# ESP32_modul.net
KiCad netlist of a schematic drawn in EAGLE
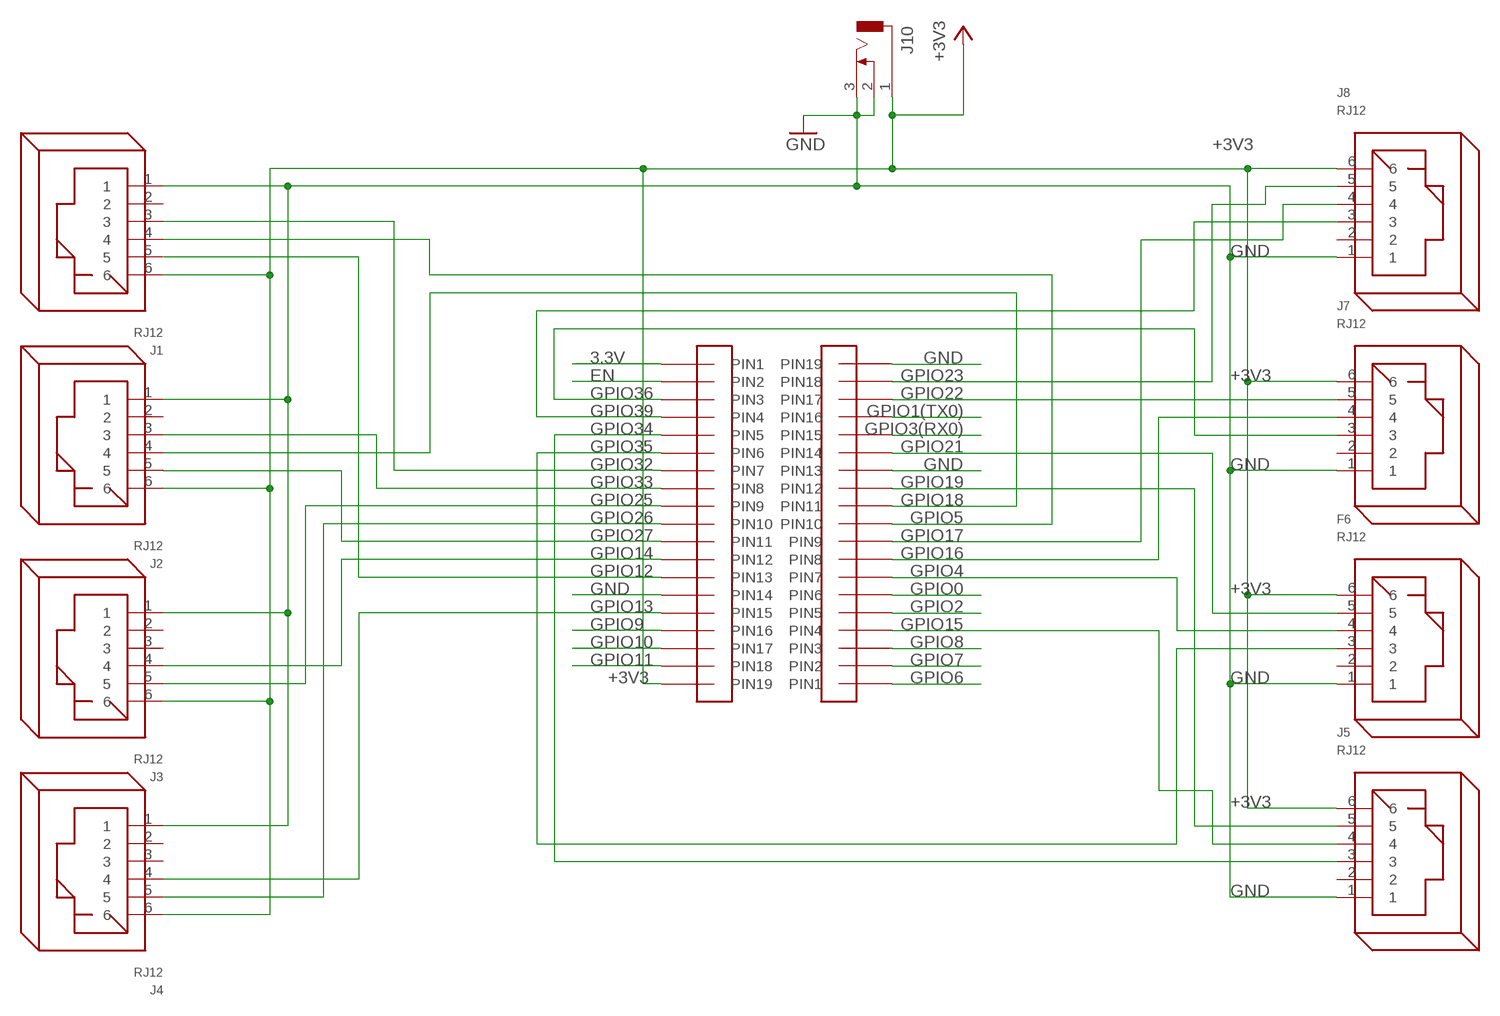
[diagram p0: schematic, sheet 1]

(export (version "E")
  (design (tool "Eeschema 10.0.6"))
  (components
    (comp (ref "F6")
      (value "RJ12")
      (footprint "eagle-import:RJ12")
      (libsource (lib "eagle-import") (part "RJ12"))
    )
    (comp (ref "J1")
      (value "RJ12")
      (footprint "eagle-import:RJ12")
      (libsource (lib "eagle-import") (part "RJ12"))
    )
    (comp (ref "J2")
      (value "RJ12")
      (footprint "eagle-import:RJ12")
      (libsource (lib "eagle-import") (part "RJ12"))
    )
    (comp (ref "J3")
      (value "RJ12")
      (footprint "eagle-import:RJ12")
      (libsource (lib "eagle-import") (part "RJ12"))
    )
    (comp (ref "J4")
      (value "RJ12")
      (footprint "eagle-import:RJ12")
      (libsource (lib "eagle-import") (part "RJ12"))
    )
    (comp (ref "J5")
      (value "RJ12")
      (footprint "eagle-import:RJ12")
      (libsource (lib "eagle-import") (part "RJ12"))
    )
    (comp (ref "J7")
      (value "RJ12")
      (footprint "eagle-import:RJ12")
      (libsource (lib "eagle-import") (part "RJ12"))
    )
    (comp (ref "J8")
      (value "RJ12")
      (footprint "eagle-import:RJ12")
      (libsource (lib "eagle-import") (part "RJ12"))
    )
    (comp (ref "J10")
      (value "DCJ0303")
      (footprint "eagle-import:DCJ0303")
      (libsource (lib "eagle-import") (part "DCJ0303"))
    )
    (comp (ref "U$1")
      (value "F-1X19")
      (footprint "eagle-import:F-1X19")
      (libsource (lib "eagle-import") (part "F-1X19"))
    )
    (comp (ref "U$2")
      (value "F-1X19")
      (footprint "eagle-import:F-1X19")
      (libsource (lib "eagle-import") (part "F-1X19"))
    )
  )
  (nets
    (net (code "1") (name "+3V3") (class "Default")
      (node (ref "F6") (pin "6") (pinfunction "6_6") (pintype "bidirectional"))
      (node (ref "J1") (pin "6") (pinfunction "6_6") (pintype "bidirectional"))
      (node (ref "J10") (pin "1") (pinfunction "1_1") (pintype "passive"))
      (node (ref "J2") (pin "6") (pinfunction "6_6") (pintype "bidirectional"))
      (node (ref "J3") (pin "6") (pinfunction "6_6") (pintype "bidirectional"))
      (node (ref "J4") (pin "6") (pinfunction "6_6") (pintype "bidirectional"))
      (node (ref "J5") (pin "6") (pinfunction "6_6") (pintype "bidirectional"))
      (node (ref "J7") (pin "6") (pinfunction "6_6") (pintype "bidirectional"))
      (node (ref "J8") (pin "6") (pinfunction "6_6") (pintype "bidirectional"))
      (node (ref "U$1") (pin "P$19") (pinfunction "PIN19_P$19") (pintype "bidirectional"))
    )
    (net (code "2") (name "/3.3V") (class "Default")
      (node (ref "U$1") (pin "P$1") (pinfunction "PIN1_P$1") (pintype "bidirectional"))
    )
    (net (code "3") (name "/EN") (class "Default")
      (node (ref "U$1") (pin "P$2") (pinfunction "PIN2_P$2") (pintype "bidirectional"))
    )
    (net (code "4") (name "/GPIO0") (class "Default")
      (node (ref "U$2") (pin "P$6") (pinfunction "PIN6_P$6") (pintype "bidirectional"))
    )
    (net (code "5") (name "/GPIO1(TX0)") (class "Default")
      (node (ref "U$2") (pin "P$16") (pinfunction "PIN16_P$16") (pintype "bidirectional"))
    )
    (net (code "6") (name "/GPIO2") (class "Default")
      (node (ref "U$2") (pin "P$5") (pinfunction "PIN5_P$5") (pintype "bidirectional"))
    )
    (net (code "7") (name "/GPIO3(RX0)") (class "Default")
      (node (ref "U$2") (pin "P$15") (pinfunction "PIN15_P$15") (pintype "bidirectional"))
    )
    (net (code "8") (name "/GPIO4") (class "Default")
      (node (ref "F6") (pin "4") (pinfunction "4_4") (pintype "bidirectional"))
      (node (ref "U$2") (pin "P$7") (pinfunction "PIN7_P$7") (pintype "bidirectional"))
    )
    (net (code "9") (name "/GPIO5") (class "Default")
      (node (ref "J1") (pin "4") (pinfunction "4_4") (pintype "bidirectional"))
      (node (ref "U$2") (pin "P$10") (pinfunction "PIN10_P$10") (pintype "bidirectional"))
    )
    (net (code "10") (name "/GPIO6") (class "Default")
      (node (ref "U$2") (pin "P$1") (pinfunction "PIN1_P$1") (pintype "bidirectional"))
    )
    (net (code "11") (name "/GPIO7") (class "Default")
      (node (ref "U$2") (pin "P$2") (pinfunction "PIN2_P$2") (pintype "bidirectional"))
    )
    (net (code "12") (name "/GPIO8") (class "Default")
      (node (ref "U$2") (pin "P$3") (pinfunction "PIN3_P$3") (pintype "bidirectional"))
    )
    (net (code "13") (name "/GPIO9") (class "Default")
      (node (ref "U$1") (pin "P$16") (pinfunction "PIN16_P$16") (pintype "bidirectional"))
    )
    (net (code "14") (name "/GPIO10") (class "Default")
      (node (ref "U$1") (pin "P$17") (pinfunction "PIN17_P$17") (pintype "bidirectional"))
    )
    (net (code "15") (name "/GPIO11") (class "Default")
      (node (ref "U$1") (pin "P$18") (pinfunction "PIN18_P$18") (pintype "bidirectional"))
    )
    (net (code "16") (name "/GPIO12") (class "Default")
      (node (ref "J1") (pin "5") (pinfunction "5_5") (pintype "bidirectional"))
      (node (ref "U$1") (pin "P$13") (pinfunction "PIN13_P$13") (pintype "bidirectional"))
    )
    (net (code "17") (name "/GPIO13") (class "Default")
      (node (ref "J4") (pin "4") (pinfunction "4_4") (pintype "bidirectional"))
      (node (ref "U$1") (pin "P$15") (pinfunction "PIN15_P$15") (pintype "bidirectional"))
    )
    (net (code "18") (name "/GPIO14") (class "Default")
      (node (ref "J3") (pin "4") (pinfunction "4_4") (pintype "bidirectional"))
      (node (ref "U$1") (pin "P$12") (pinfunction "PIN12_P$12") (pintype "bidirectional"))
    )
    (net (code "19") (name "/GPIO15") (class "Default")
      (node (ref "J5") (pin "4") (pinfunction "4_4") (pintype "bidirectional"))
      (node (ref "U$2") (pin "P$4") (pinfunction "PIN4_P$4") (pintype "bidirectional"))
    )
    (net (code "20") (name "/GPIO16") (class "Default")
      (node (ref "J7") (pin "4") (pinfunction "4_4") (pintype "bidirectional"))
      (node (ref "U$2") (pin "P$8") (pinfunction "PIN8_P$8") (pintype "bidirectional"))
    )
    (net (code "21") (name "/GPIO17") (class "Default")
      (node (ref "J8") (pin "4") (pinfunction "4_4") (pintype "bidirectional"))
      (node (ref "U$2") (pin "P$9") (pinfunction "PIN9_P$9") (pintype "bidirectional"))
    )
    (net (code "22") (name "/GPIO18") (class "Default")
      (node (ref "J2") (pin "4") (pinfunction "4_4") (pintype "bidirectional"))
      (node (ref "U$2") (pin "P$11") (pinfunction "PIN11_P$11") (pintype "bidirectional"))
    )
    (net (code "23") (name "/GPIO19") (class "Default")
      (node (ref "J5") (pin "5") (pinfunction "5_5") (pintype "bidirectional"))
      (node (ref "U$2") (pin "P$12") (pinfunction "PIN12_P$12") (pintype "bidirectional"))
    )
    (net (code "24") (name "/GPIO21") (class "Default")
      (node (ref "F6") (pin "5") (pinfunction "5_5") (pintype "bidirectional"))
      (node (ref "U$2") (pin "P$14") (pinfunction "PIN14_P$14") (pintype "bidirectional"))
    )
    (net (code "25") (name "/GPIO22") (class "Default")
      (node (ref "J7") (pin "5") (pinfunction "5_5") (pintype "bidirectional"))
      (node (ref "U$2") (pin "P$17") (pinfunction "PIN17_P$17") (pintype "bidirectional"))
    )
    (net (code "26") (name "/GPIO23") (class "Default")
      (node (ref "J8") (pin "5") (pinfunction "5_5") (pintype "bidirectional"))
      (node (ref "U$2") (pin "P$18") (pinfunction "PIN18_P$18") (pintype "bidirectional"))
    )
    (net (code "27") (name "/GPIO25") (class "Default")
      (node (ref "J3") (pin "5") (pinfunction "5_5") (pintype "bidirectional"))
      (node (ref "U$1") (pin "P$9") (pinfunction "PIN9_P$9") (pintype "bidirectional"))
    )
    (net (code "28") (name "/GPIO26") (class "Default")
      (node (ref "J4") (pin "5") (pinfunction "5_5") (pintype "bidirectional"))
      (node (ref "U$1") (pin "P$10") (pinfunction "PIN10_P$10") (pintype "bidirectional"))
    )
    (net (code "29") (name "/GPIO27") (class "Default")
      (node (ref "J2") (pin "5") (pinfunction "5_5") (pintype "bidirectional"))
      (node (ref "U$1") (pin "P$11") (pinfunction "PIN11_P$11") (pintype "bidirectional"))
    )
    (net (code "30") (name "/GPIO32") (class "Default")
      (node (ref "J1") (pin "3") (pinfunction "3_3") (pintype "bidirectional"))
      (node (ref "U$1") (pin "P$7") (pinfunction "PIN7_P$7") (pintype "bidirectional"))
    )
    (net (code "31") (name "/GPIO33") (class "Default")
      (node (ref "J2") (pin "3") (pinfunction "3_3") (pintype "bidirectional"))
      (node (ref "U$1") (pin "P$8") (pinfunction "PIN8_P$8") (pintype "bidirectional"))
    )
    (net (code "32") (name "/GPIO34") (class "Default")
      (node (ref "J5") (pin "3") (pinfunction "3_3") (pintype "bidirectional"))
      (node (ref "U$1") (pin "P$5") (pinfunction "PIN5_P$5") (pintype "bidirectional"))
    )
    (net (code "33") (name "/GPIO35") (class "Default")
      (node (ref "F6") (pin "3") (pinfunction "3_3") (pintype "bidirectional"))
      (node (ref "U$1") (pin "P$6") (pinfunction "PIN6_P$6") (pintype "bidirectional"))
    )
    (net (code "34") (name "/GPIO36") (class "Default")
      (node (ref "J7") (pin "3") (pinfunction "3_3") (pintype "bidirectional"))
      (node (ref "U$1") (pin "P$3") (pinfunction "PIN3_P$3") (pintype "bidirectional"))
    )
    (net (code "35") (name "/GPIO39") (class "Default")
      (node (ref "J8") (pin "3") (pinfunction "3_3") (pintype "bidirectional"))
      (node (ref "U$1") (pin "P$4") (pinfunction "PIN4_P$4") (pintype "bidirectional"))
    )
    (net (code "36") (name "GND") (class "Default")
      (node (ref "F6") (pin "1") (pinfunction "1_1") (pintype "bidirectional"))
      (node (ref "J1") (pin "1") (pinfunction "1_1") (pintype "bidirectional"))
      (node (ref "J10") (pin "2") (pinfunction "2_2") (pintype "passive"))
      (node (ref "J10") (pin "3") (pinfunction "3_3") (pintype "passive"))
      (node (ref "J2") (pin "1") (pinfunction "1_1") (pintype "bidirectional"))
      (node (ref "J3") (pin "1") (pinfunction "1_1") (pintype "bidirectional"))
      (node (ref "J4") (pin "1") (pinfunction "1_1") (pintype "bidirectional"))
      (node (ref "J5") (pin "1") (pinfunction "1_1") (pintype "bidirectional"))
      (node (ref "J7") (pin "1") (pinfunction "1_1") (pintype "bidirectional"))
      (node (ref "J8") (pin "1") (pinfunction "1_1") (pintype "bidirectional"))
      (node (ref "U$1") (pin "P$14") (pinfunction "PIN14_P$14") (pintype "bidirectional"))
      (node (ref "U$2") (pin "P$13") (pinfunction "PIN13_P$13") (pintype "bidirectional"))
      (node (ref "U$2") (pin "P$19") (pinfunction "PIN19_P$19") (pintype "bidirectional"))
    )
    (net (code "37") (name "unconnected-(F6-Pad2)") (class "Default")
      (node (ref "F6") (pin "2") (pinfunction "2_2") (pintype "bidirectional"))
    )
    (net (code "38") (name "unconnected-(J1-Pad2)") (class "Default")
      (node (ref "J1") (pin "2") (pinfunction "2_2") (pintype "bidirectional"))
    )
    (net (code "39") (name "unconnected-(J2-Pad2)") (class "Default")
      (node (ref "J2") (pin "2") (pinfunction "2_2") (pintype "bidirectional"))
    )
    (net (code "40") (name "unconnected-(J3-Pad2)") (class "Default")
      (node (ref "J3") (pin "2") (pinfunction "2_2") (pintype "bidirectional"))
    )
    (net (code "41") (name "unconnected-(J3-Pad3)") (class "Default")
      (node (ref "J3") (pin "3") (pinfunction "3_3") (pintype "bidirectional"))
    )
    (net (code "42") (name "unconnected-(J4-Pad2)") (class "Default")
      (node (ref "J4") (pin "2") (pinfunction "2_2") (pintype "bidirectional"))
    )
    (net (code "43") (name "unconnected-(J4-Pad3)") (class "Default")
      (node (ref "J4") (pin "3") (pinfunction "3_3") (pintype "bidirectional"))
    )
    (net (code "44") (name "unconnected-(J5-Pad2)") (class "Default")
      (node (ref "J5") (pin "2") (pinfunction "2_2") (pintype "bidirectional"))
    )
    (net (code "45") (name "unconnected-(J7-Pad2)") (class "Default")
      (node (ref "J7") (pin "2") (pinfunction "2_2") (pintype "bidirectional"))
    )
    (net (code "46") (name "unconnected-(J8-Pad2)") (class "Default")
      (node (ref "J8") (pin "2") (pinfunction "2_2") (pintype "bidirectional"))
    )
  )
)
